# detector.net
KiCad netlist of a schematic drawn in EAGLE
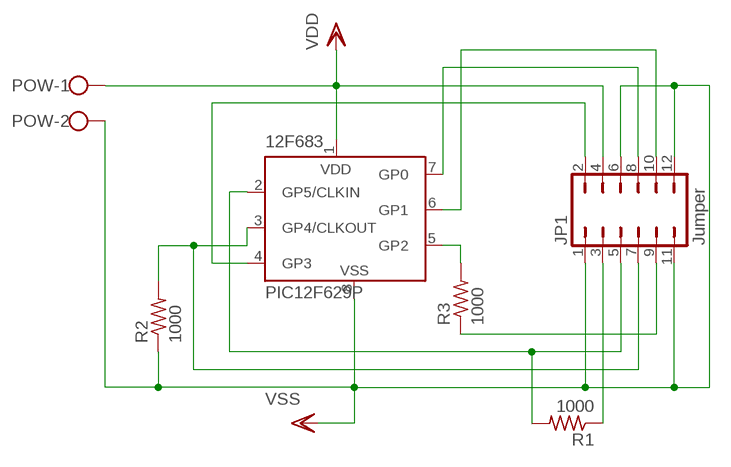
[diagram p0: schematic, sheet 1]

(export (version "E")
  (design (tool "Eeschema 10.0.6"))
  (components
    (comp (ref "12F683")
      (value "PIC12F629P")
      (footprint "eagle-import:DIL8")
      (fields (field (name "MF") "MICROCHIP") (field (name "MPN") "PIC12F629-I/P"))
      (libsource (lib "eagle-import") (part "PIC12F6P29"))
    )
    (comp (ref "JP1")
      (value "Jumper")
      (footprint "eagle-import:JP6Q")
      (libsource (lib "eagle-import") (part "JP6Q"))
    )
    (comp (ref "POW")
      (value "W237-102")
      (footprint "eagle-import:W237-102")
      (fields (field (name "MPN") "237-102"))
      (libsource (lib "eagle-import") (part "W237-102"))
    )
    (comp (ref "R1")
      (value "1000")
      (footprint "eagle-import:0207_10")
      (libsource (lib "eagle-import") (part "R-US_0207/10"))
    )
    (comp (ref "R2")
      (value "1000")
      (footprint "eagle-import:0207_10")
      (libsource (lib "eagle-import") (part "R-US_0207/10"))
    )
    (comp (ref "R3")
      (value "1000")
      (footprint "eagle-import:0207_10")
      (libsource (lib "eagle-import") (part "R-US_0207/10"))
    )
  )
  (nets
    (net (code "1") (name "Net-(12F683-GP0)") (class "Default")
      (node (ref "12F683") (pin "7") (pinfunction "GP0_7") (pintype "bidirectional"))
      (node (ref "JP1") (pin "8") (pinfunction "8_8") (pintype "passive"))
    )
    (net (code "2") (name "Net-(12F683-GP1)") (class "Default")
      (node (ref "12F683") (pin "6") (pinfunction "GP1_6") (pintype "bidirectional"))
      (node (ref "JP1") (pin "10") (pinfunction "10_10") (pintype "passive"))
    )
    (net (code "3") (name "Net-(12F683-GP2)") (class "Default")
      (node (ref "12F683") (pin "5") (pinfunction "GP2_5") (pintype "bidirectional"))
      (node (ref "R3") (pin "2") (pinfunction "2_2") (pintype "passive"))
    )
    (net (code "4") (name "Net-(12F683-GP3)") (class "Default")
      (node (ref "12F683") (pin "4") (pinfunction "GP3_4") (pintype "input"))
      (node (ref "JP1") (pin "2") (pinfunction "2_2") (pintype "passive"))
    )
    (net (code "5") (name "Net-(12F683-GP4{slash}CLKOUT)") (class "Default")
      (node (ref "12F683") (pin "3") (pinfunction "GP4/CLKOUT_3") (pintype "bidirectional"))
      (node (ref "JP1") (pin "7") (pinfunction "7_7") (pintype "passive"))
      (node (ref "R2") (pin "2") (pinfunction "2_2") (pintype "passive"))
    )
    (net (code "6") (name "Net-(12F683-GP5{slash}CLKIN)") (class "Default")
      (node (ref "12F683") (pin "2") (pinfunction "GP5/CLKIN_2") (pintype "bidirectional"))
      (node (ref "JP1") (pin "5") (pinfunction "5_5") (pintype "passive"))
      (node (ref "R1") (pin "2") (pinfunction "2_2") (pintype "passive"))
    )
    (net (code "7") (name "Net-(JP1-Pad3)") (class "Default")
      (node (ref "JP1") (pin "3") (pinfunction "3_3") (pintype "passive"))
      (node (ref "R1") (pin "1") (pinfunction "1_1") (pintype "passive"))
    )
    (net (code "8") (name "Net-(JP1-Pad9)") (class "Default")
      (node (ref "JP1") (pin "9") (pinfunction "9_9") (pintype "passive"))
      (node (ref "R3") (pin "1") (pinfunction "1_1") (pintype "passive"))
    )
    (net (code "9") (name "VDD") (class "Default")
      (node (ref "12F683") (pin "1") (pinfunction "VDD_1") (pintype "power_in"))
      (node (ref "JP1") (pin "4") (pinfunction "4_4") (pintype "passive"))
      (node (ref "POW") (pin "1") (pinfunction "KL_1") (pintype "passive"))
    )
    (net (code "10") (name "VSS") (class "Default")
      (node (ref "12F683") (pin "8") (pinfunction "VSS_8") (pintype "power_in"))
      (node (ref "JP1") (pin "1") (pinfunction "1_1") (pintype "passive"))
      (node (ref "JP1") (pin "11") (pinfunction "11_11") (pintype "passive"))
      (node (ref "JP1") (pin "12") (pinfunction "12_12") (pintype "passive"))
      (node (ref "JP1") (pin "6") (pinfunction "6_6") (pintype "passive"))
      (node (ref "POW") (pin "2") (pinfunction "KL_2") (pintype "passive"))
      (node (ref "R2") (pin "1") (pinfunction "1_1") (pintype "passive"))
    )
  )
)
